# HC-base_revA.net
KiCad netlist of a schematic drawn in EAGLE
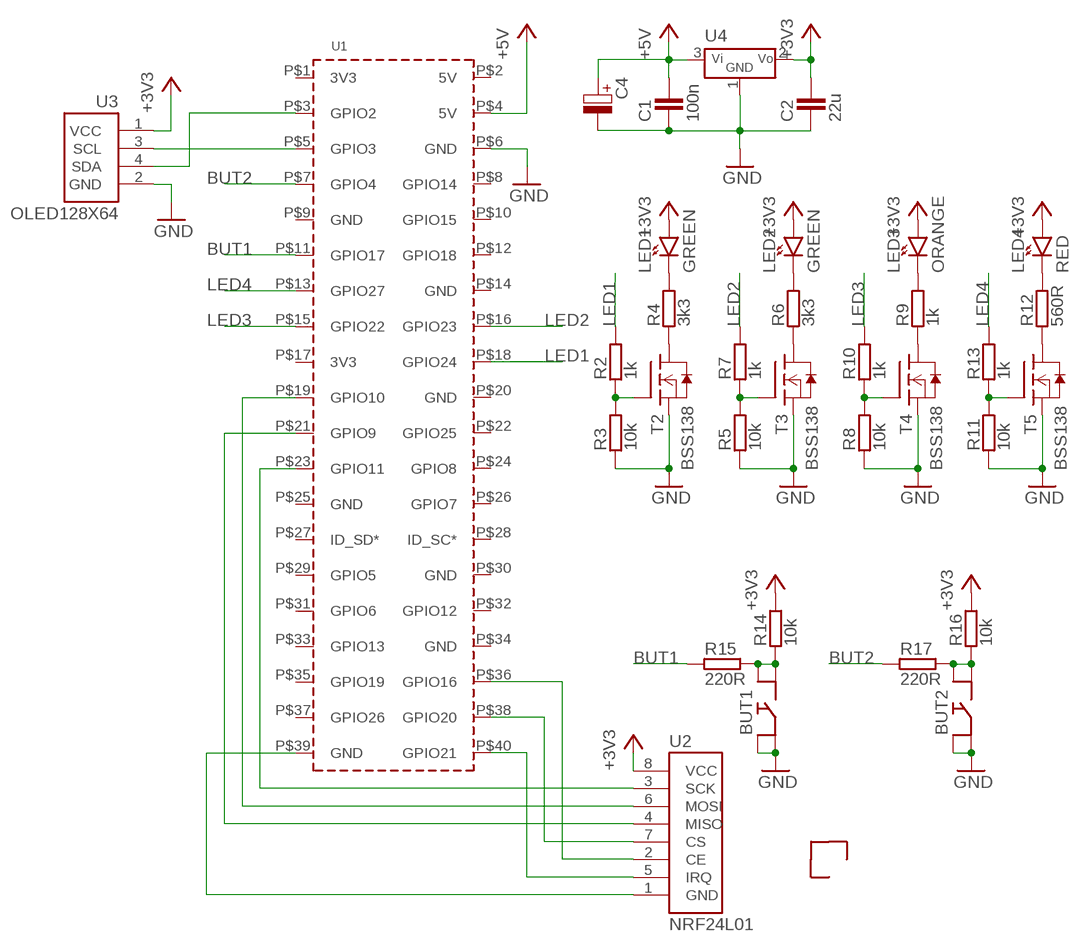
[diagram p0: schematic, sheet 1]

(export (version "E")
  (design (tool "Eeschema 10.0.6"))
  (components
    (comp (ref "BUT1")
      (value "BUTTON'SMD'")
      (footprint "eagle-import:BUTTON_SMD")
      (libsource (lib "eagle-import") (part "BUTTON'SMD'"))
    )
    (comp (ref "BUT2")
      (value "BUTTON'SMD'")
      (footprint "eagle-import:BUTTON_SMD")
      (libsource (lib "eagle-import") (part "BUTTON'SMD'"))
    )
    (comp (ref "C1")
      (value "100n")
      (footprint "eagle-import:C0805")
      (libsource (lib "eagle-import") (part "C-CERAMIC'SMD'"))
    )
    (comp (ref "C2")
      (value "22u")
      (footprint "eagle-import:C0805")
      (libsource (lib "eagle-import") (part "C-CERAMIC'SMD'"))
    )
    (comp (ref "C4")
      (value "C-POLY'6.5MM'")
      (footprint "eagle-import:ELYT-6MM5")
      (libsource (lib "eagle-import") (part "C-POLY'6.5MM'"))
    )
    (comp (ref "LED1")
      (value "GREEN")
      (footprint "eagle-import:LED0805")
      (libsource (lib "eagle-import") (part "LED'SMD'"))
    )
    (comp (ref "LED2")
      (value "GREEN")
      (footprint "eagle-import:LED0805")
      (libsource (lib "eagle-import") (part "LED'SMD'"))
    )
    (comp (ref "LED3")
      (value "ORANGE")
      (footprint "eagle-import:LED0805")
      (libsource (lib "eagle-import") (part "LED'SMD'"))
    )
    (comp (ref "LED4")
      (value "RED")
      (footprint "eagle-import:LED0805")
      (libsource (lib "eagle-import") (part "LED'SMD'"))
    )
    (comp (ref "R2")
      (value "1k")
      (footprint "eagle-import:R0805")
      (libsource (lib "eagle-import") (part "R'2'"))
    )
    (comp (ref "R3")
      (value "10k")
      (footprint "eagle-import:R0805")
      (libsource (lib "eagle-import") (part "R'2'"))
    )
    (comp (ref "R4")
      (value "3k3")
      (footprint "eagle-import:R0805")
      (libsource (lib "eagle-import") (part "R'2'"))
    )
    (comp (ref "R5")
      (value "10k")
      (footprint "eagle-import:R0805")
      (libsource (lib "eagle-import") (part "R'2'"))
    )
    (comp (ref "R6")
      (value "3k3")
      (footprint "eagle-import:R0805")
      (libsource (lib "eagle-import") (part "R'2'"))
    )
    (comp (ref "R7")
      (value "1k")
      (footprint "eagle-import:R0805")
      (libsource (lib "eagle-import") (part "R'2'"))
    )
    (comp (ref "R8")
      (value "10k")
      (footprint "eagle-import:R0805")
      (libsource (lib "eagle-import") (part "R'2'"))
    )
    (comp (ref "R9")
      (value "1k")
      (footprint "eagle-import:R0805")
      (libsource (lib "eagle-import") (part "R'2'"))
    )
    (comp (ref "R10")
      (value "1k")
      (footprint "eagle-import:R0805")
      (libsource (lib "eagle-import") (part "R'2'"))
    )
    (comp (ref "R11")
      (value "10k")
      (footprint "eagle-import:R0805")
      (libsource (lib "eagle-import") (part "R'2'"))
    )
    (comp (ref "R12")
      (value "560R")
      (footprint "eagle-import:R0805")
      (libsource (lib "eagle-import") (part "R'2'"))
    )
    (comp (ref "R13")
      (value "1k")
      (footprint "eagle-import:R0805")
      (libsource (lib "eagle-import") (part "R'2'"))
    )
    (comp (ref "R14")
      (value "10k")
      (footprint "eagle-import:R0805")
      (libsource (lib "eagle-import") (part "R'2'"))
    )
    (comp (ref "R15")
      (value "220R")
      (footprint "eagle-import:R0805")
      (libsource (lib "eagle-import") (part "R'2'"))
    )
    (comp (ref "R16")
      (value "10k")
      (footprint "eagle-import:R0805")
      (libsource (lib "eagle-import") (part "R'2'"))
    )
    (comp (ref "R17")
      (value "220R")
      (footprint "eagle-import:R0805")
      (libsource (lib "eagle-import") (part "R'2'"))
    )
    (comp (ref "T2")
      (value "BSS138")
      (footprint "eagle-import:SOT23")
      (libsource (lib "eagle-import") (part "BSS138"))
    )
    (comp (ref "T3")
      (value "BSS138")
      (footprint "eagle-import:SOT23")
      (libsource (lib "eagle-import") (part "BSS138"))
    )
    (comp (ref "T4")
      (value "BSS138")
      (footprint "eagle-import:SOT23")
      (libsource (lib "eagle-import") (part "BSS138"))
    )
    (comp (ref "T5")
      (value "BSS138")
      (footprint "eagle-import:SOT23")
      (libsource (lib "eagle-import") (part "BSS138"))
    )
    (comp (ref "U$1")
      (value "CORNER")
      (footprint "eagle-import:CORNER")
      (libsource (lib "eagle-import") (part "CORNER"))
    )
    (comp (ref "U$2")
      (value "CORNER")
      (footprint "eagle-import:CORNER")
      (libsource (lib "eagle-import") (part "CORNER"))
    )
    (comp (ref "U$3")
      (value "CORNER")
      (footprint "eagle-import:CORNER")
      (libsource (lib "eagle-import") (part "CORNER"))
    )
    (comp (ref "U1")
      (value "RPI3_SIMPLE'PART'")
      (footprint "eagle-import:RPI3-PART")
      (libsource (lib "eagle-import") (part "RPI3_SIMPLE'PART'"))
    )
    (comp (ref "U2")
      (value "NRF24L01")
      (footprint "eagle-import:NRF24L01")
      (libsource (lib "eagle-import") (part "NRF24L01"))
    )
    (comp (ref "U3")
      (value "OLED128X64")
      (footprint "eagle-import:OLED128X64")
      (libsource (lib "eagle-import") (part "OLED128X64"))
    )
    (comp (ref "U4")
      (value "V_STAB'TS1117'")
      (footprint "eagle-import:SOT223")
      (libsource (lib "eagle-import") (part "V_STAB'TS1117'"))
    )
  )
  (nets
    (net (code "1") (name "+3V3") (class "Default")
      (node (ref "C2") (pin "2") (pinfunction "P$2_2") (pintype "bidirectional"))
      (node (ref "LED1") (pin "1") (pinfunction "A_1") (pintype "bidirectional"))
      (node (ref "LED2") (pin "1") (pinfunction "A_1") (pintype "bidirectional"))
      (node (ref "LED3") (pin "1") (pinfunction "A_1") (pintype "bidirectional"))
      (node (ref "LED4") (pin "1") (pinfunction "A_1") (pintype "bidirectional"))
      (node (ref "R14") (pin "2") (pinfunction "P$2_2") (pintype "bidirectional"))
      (node (ref "R16") (pin "2") (pinfunction "P$2_2") (pintype "bidirectional"))
      (node (ref "U2") (pin "8") (pinfunction "VCC_8") (pintype "power_in"))
      (node (ref "U3") (pin "1") (pinfunction "VCC_1") (pintype "power_in"))
      (node (ref "U4") (pin "2") (pinfunction "VOUT_2") (pintype "power_in"))
    )
    (net (code "2") (name "+5V") (class "Default")
      (node (ref "C1") (pin "2") (pinfunction "P$2_2") (pintype "bidirectional"))
      (node (ref "C4") (pin "+") (pinfunction "POS_+") (pintype "bidirectional"))
      (node (ref "U1") (pin "P$4") (pinfunction "5V_P$4") (pintype "bidirectional"))
      (node (ref "U4") (pin "3") (pinfunction "VIN_3") (pintype "power_in"))
    )
    (net (code "3") (name "/BUT1") (class "Default")
      (node (ref "R15") (pin "1") (pinfunction "P$1_1") (pintype "bidirectional"))
      (node (ref "U1") (pin "P$11") (pinfunction "GPIO17_P$11") (pintype "bidirectional"))
    )
    (net (code "4") (name "/BUT2") (class "Default")
      (node (ref "R17") (pin "1") (pinfunction "P$1_1") (pintype "bidirectional"))
      (node (ref "U1") (pin "P$7") (pinfunction "GPIO4_P$7") (pintype "bidirectional"))
    )
    (net (code "5") (name "/LED1") (class "Default")
      (node (ref "R2") (pin "2") (pinfunction "P$2_2") (pintype "bidirectional"))
      (node (ref "U1") (pin "P$18") (pinfunction "GPIO24_P$18") (pintype "bidirectional"))
    )
    (net (code "6") (name "/LED2") (class "Default")
      (node (ref "R7") (pin "2") (pinfunction "P$2_2") (pintype "bidirectional"))
      (node (ref "U1") (pin "P$16") (pinfunction "GPIO23_P$16") (pintype "bidirectional"))
    )
    (net (code "7") (name "/LED3") (class "Default")
      (node (ref "R10") (pin "2") (pinfunction "P$2_2") (pintype "bidirectional"))
      (node (ref "U1") (pin "P$15") (pinfunction "GPIO22_P$15") (pintype "bidirectional"))
    )
    (net (code "8") (name "/LED4") (class "Default")
      (node (ref "R13") (pin "2") (pinfunction "P$2_2") (pintype "bidirectional"))
      (node (ref "U1") (pin "P$13") (pinfunction "GPIO27_P$13") (pintype "bidirectional"))
    )
    (net (code "9") (name "GND") (class "Default")
      (node (ref "BUT1") (pin "1") (pinfunction "4_1") (pintype "bidirectional"))
      (node (ref "BUT1") (pin "2") (pinfunction "2_2") (pintype "bidirectional"))
      (node (ref "BUT2") (pin "1") (pinfunction "4_1") (pintype "bidirectional"))
      (node (ref "BUT2") (pin "2") (pinfunction "2_2") (pintype "bidirectional"))
      (node (ref "C1") (pin "1") (pinfunction "P$1_1") (pintype "bidirectional"))
      (node (ref "C2") (pin "1") (pinfunction "P$1_1") (pintype "bidirectional"))
      (node (ref "C4") (pin "-") (pinfunction "NEG_-") (pintype "bidirectional"))
      (node (ref "R11") (pin "1") (pinfunction "P$1_1") (pintype "bidirectional"))
      (node (ref "R3") (pin "1") (pinfunction "P$1_1") (pintype "bidirectional"))
      (node (ref "R5") (pin "1") (pinfunction "P$1_1") (pintype "bidirectional"))
      (node (ref "R8") (pin "1") (pinfunction "P$1_1") (pintype "bidirectional"))
      (node (ref "T2") (pin "2") (pinfunction "S_2") (pintype "passive"))
      (node (ref "T3") (pin "2") (pinfunction "S_2") (pintype "passive"))
      (node (ref "T4") (pin "2") (pinfunction "S_2") (pintype "passive"))
      (node (ref "T5") (pin "2") (pinfunction "S_2") (pintype "passive"))
      (node (ref "U1") (pin "P$6") (pinfunction "GND_P$6") (pintype "bidirectional"))
      (node (ref "U3") (pin "2") (pinfunction "GND_2") (pintype "power_in"))
      (node (ref "U4") (pin "1") (pinfunction "GND_1") (pintype "power_in"))
    )
    (net (code "10") (name "Net-(BUT1-1)") (class "Default")
      (node (ref "BUT1") (pin "3") (pinfunction "1_3") (pintype "bidirectional"))
      (node (ref "BUT1") (pin "4") (pinfunction "3_4") (pintype "bidirectional"))
      (node (ref "R14") (pin "1") (pinfunction "P$1_1") (pintype "bidirectional"))
      (node (ref "R15") (pin "2") (pinfunction "P$2_2") (pintype "bidirectional"))
    )
    (net (code "11") (name "Net-(BUT2-1)") (class "Default")
      (node (ref "BUT2") (pin "3") (pinfunction "1_3") (pintype "bidirectional"))
      (node (ref "BUT2") (pin "4") (pinfunction "3_4") (pintype "bidirectional"))
      (node (ref "R16") (pin "1") (pinfunction "P$1_1") (pintype "bidirectional"))
      (node (ref "R17") (pin "2") (pinfunction "P$2_2") (pintype "bidirectional"))
    )
    (net (code "12") (name "Net-(LED1-K)") (class "Default")
      (node (ref "LED1") (pin "2") (pinfunction "K_2") (pintype "bidirectional"))
      (node (ref "R4") (pin "2") (pinfunction "P$2_2") (pintype "bidirectional"))
    )
    (net (code "13") (name "Net-(LED2-K)") (class "Default")
      (node (ref "LED2") (pin "2") (pinfunction "K_2") (pintype "bidirectional"))
      (node (ref "R6") (pin "2") (pinfunction "P$2_2") (pintype "bidirectional"))
    )
    (net (code "14") (name "Net-(LED3-K)") (class "Default")
      (node (ref "LED3") (pin "2") (pinfunction "K_2") (pintype "bidirectional"))
      (node (ref "R9") (pin "2") (pinfunction "P$2_2") (pintype "bidirectional"))
    )
    (net (code "15") (name "Net-(LED4-K)") (class "Default")
      (node (ref "LED4") (pin "2") (pinfunction "K_2") (pintype "bidirectional"))
      (node (ref "R12") (pin "2") (pinfunction "P$2_2") (pintype "bidirectional"))
    )
    (net (code "16") (name "Net-(R2-P$1)") (class "Default")
      (node (ref "R2") (pin "1") (pinfunction "P$1_1") (pintype "bidirectional"))
      (node (ref "R3") (pin "2") (pinfunction "P$2_2") (pintype "bidirectional"))
      (node (ref "T2") (pin "1") (pinfunction "G_1") (pintype "passive"))
    )
    (net (code "17") (name "Net-(R4-P$1)") (class "Default")
      (node (ref "R4") (pin "1") (pinfunction "P$1_1") (pintype "bidirectional"))
      (node (ref "T2") (pin "3") (pinfunction "D_3") (pintype "passive"))
    )
    (net (code "18") (name "Net-(R5-P$2)") (class "Default")
      (node (ref "R5") (pin "2") (pinfunction "P$2_2") (pintype "bidirectional"))
      (node (ref "R7") (pin "1") (pinfunction "P$1_1") (pintype "bidirectional"))
      (node (ref "T3") (pin "1") (pinfunction "G_1") (pintype "passive"))
    )
    (net (code "19") (name "Net-(R6-P$1)") (class "Default")
      (node (ref "R6") (pin "1") (pinfunction "P$1_1") (pintype "bidirectional"))
      (node (ref "T3") (pin "3") (pinfunction "D_3") (pintype "passive"))
    )
    (net (code "20") (name "Net-(R9-P$1)") (class "Default")
      (node (ref "R9") (pin "1") (pinfunction "P$1_1") (pintype "bidirectional"))
      (node (ref "T4") (pin "3") (pinfunction "D_3") (pintype "passive"))
    )
    (net (code "21") (name "Net-(R10-P$1)") (class "Default")
      (node (ref "R10") (pin "1") (pinfunction "P$1_1") (pintype "bidirectional"))
      (node (ref "R8") (pin "2") (pinfunction "P$2_2") (pintype "bidirectional"))
      (node (ref "T4") (pin "1") (pinfunction "G_1") (pintype "passive"))
    )
    (net (code "22") (name "Net-(R11-P$2)") (class "Default")
      (node (ref "R11") (pin "2") (pinfunction "P$2_2") (pintype "bidirectional"))
      (node (ref "R13") (pin "1") (pinfunction "P$1_1") (pintype "bidirectional"))
      (node (ref "T5") (pin "1") (pinfunction "G_1") (pintype "passive"))
    )
    (net (code "23") (name "Net-(R12-P$1)") (class "Default")
      (node (ref "R12") (pin "1") (pinfunction "P$1_1") (pintype "bidirectional"))
      (node (ref "T5") (pin "3") (pinfunction "D_3") (pintype "passive"))
    )
    (net (code "24") (name "Net-(U1-GPIO2)") (class "Default")
      (node (ref "U1") (pin "P$3") (pinfunction "GPIO2_P$3") (pintype "bidirectional"))
      (node (ref "U3") (pin "4") (pinfunction "SDA_4") (pintype "bidirectional"))
    )
    (net (code "25") (name "Net-(U1-GPIO3)") (class "Default")
      (node (ref "U1") (pin "P$5") (pinfunction "GPIO3_P$5") (pintype "bidirectional"))
      (node (ref "U3") (pin "3") (pinfunction "SCL_3") (pintype "bidirectional"))
    )
    (net (code "26") (name "Net-(U1-GPIO9)") (class "Default")
      (node (ref "U1") (pin "P$21") (pinfunction "GPIO9_P$21") (pintype "bidirectional"))
      (node (ref "U2") (pin "4") (pinfunction "MISO_4") (pintype "bidirectional"))
    )
    (net (code "27") (name "Net-(U1-GPIO10)") (class "Default")
      (node (ref "U1") (pin "P$19") (pinfunction "GPIO10_P$19") (pintype "bidirectional"))
      (node (ref "U2") (pin "6") (pinfunction "MOSI_6") (pintype "bidirectional"))
    )
    (net (code "28") (name "Net-(U1-GPIO11)") (class "Default")
      (node (ref "U1") (pin "P$23") (pinfunction "GPIO11_P$23") (pintype "bidirectional"))
      (node (ref "U2") (pin "3") (pinfunction "SCK_3") (pintype "bidirectional"))
    )
    (net (code "29") (name "Net-(U1-GPIO16)") (class "Default")
      (node (ref "U1") (pin "P$36") (pinfunction "GPIO16_P$36") (pintype "bidirectional"))
      (node (ref "U2") (pin "2") (pinfunction "CE_2") (pintype "bidirectional"))
    )
    (net (code "30") (name "Net-(U1-GPIO20)") (class "Default")
      (node (ref "U1") (pin "P$38") (pinfunction "GPIO20_P$38") (pintype "bidirectional"))
      (node (ref "U2") (pin "7") (pinfunction "CS_7") (pintype "bidirectional"))
    )
    (net (code "31") (name "Net-(U1-GPIO21)") (class "Default")
      (node (ref "U1") (pin "P$40") (pinfunction "GPIO21_P$40") (pintype "bidirectional"))
      (node (ref "U2") (pin "5") (pinfunction "IRQ_5") (pintype "bidirectional"))
    )
    (net (code "32") (name "Net-(U2-GND)") (class "Default")
      (node (ref "U1") (pin "P$39") (pinfunction "GND_P$39") (pintype "bidirectional"))
      (node (ref "U2") (pin "1") (pinfunction "GND_1") (pintype "power_in"))
    )
    (net (code "33") (name "unconnected-(U1-3V3-PadP$1)") (class "Default")
      (node (ref "U1") (pin "P$1") (pinfunction "3V3_P$1") (pintype "bidirectional"))
    )
    (net (code "34") (name "unconnected-(U1-3V3-PadP$17)") (class "Default")
      (node (ref "U1") (pin "P$17") (pinfunction "3V3_P$17") (pintype "bidirectional"))
    )
    (net (code "35") (name "unconnected-(U1-5V-PadP$2)") (class "Default")
      (node (ref "U1") (pin "P$2") (pinfunction "5V_P$2") (pintype "bidirectional"))
    )
    (net (code "36") (name "unconnected-(U1-GND-PadP$9)") (class "Default")
      (node (ref "U1") (pin "P$9") (pinfunction "GND_P$9") (pintype "bidirectional"))
    )
    (net (code "37") (name "unconnected-(U1-GND-PadP$14)") (class "Default")
      (node (ref "U1") (pin "P$14") (pinfunction "GND_P$14") (pintype "bidirectional"))
    )
    (net (code "38") (name "unconnected-(U1-GND-PadP$20)") (class "Default")
      (node (ref "U1") (pin "P$20") (pinfunction "GND_P$20") (pintype "bidirectional"))
    )
    (net (code "39") (name "unconnected-(U1-GND-PadP$25)") (class "Default")
      (node (ref "U1") (pin "P$25") (pinfunction "GND_P$25") (pintype "bidirectional"))
    )
    (net (code "40") (name "unconnected-(U1-GND-PadP$30)") (class "Default")
      (node (ref "U1") (pin "P$30") (pinfunction "GND_P$30") (pintype "bidirectional"))
    )
    (net (code "41") (name "unconnected-(U1-GND-PadP$34)") (class "Default")
      (node (ref "U1") (pin "P$34") (pinfunction "GND_P$34") (pintype "bidirectional"))
    )
    (net (code "42") (name "unconnected-(U1-GPIO5-PadP$29)") (class "Default")
      (node (ref "U1") (pin "P$29") (pinfunction "GPIO5_P$29") (pintype "bidirectional"))
    )
    (net (code "43") (name "unconnected-(U1-GPIO6-PadP$31)") (class "Default")
      (node (ref "U1") (pin "P$31") (pinfunction "GPIO6_P$31") (pintype "bidirectional"))
    )
    (net (code "44") (name "unconnected-(U1-GPIO7-PadP$26)") (class "Default")
      (node (ref "U1") (pin "P$26") (pinfunction "GPIO7_P$26") (pintype "bidirectional"))
    )
    (net (code "45") (name "unconnected-(U1-GPIO8-PadP$24)") (class "Default")
      (node (ref "U1") (pin "P$24") (pinfunction "GPIO8_P$24") (pintype "bidirectional"))
    )
    (net (code "46") (name "unconnected-(U1-GPIO12-PadP$32)") (class "Default")
      (node (ref "U1") (pin "P$32") (pinfunction "GPIO12_P$32") (pintype "bidirectional"))
    )
    (net (code "47") (name "unconnected-(U1-GPIO13-PadP$33)") (class "Default")
      (node (ref "U1") (pin "P$33") (pinfunction "GPIO13_P$33") (pintype "bidirectional"))
    )
    (net (code "48") (name "unconnected-(U1-GPIO14-PadP$8)") (class "Default")
      (node (ref "U1") (pin "P$8") (pinfunction "GPIO14_P$8") (pintype "bidirectional"))
    )
    (net (code "49") (name "unconnected-(U1-GPIO15-PadP$10)") (class "Default")
      (node (ref "U1") (pin "P$10") (pinfunction "GPIO15_P$10") (pintype "bidirectional"))
    )
    (net (code "50") (name "unconnected-(U1-GPIO18-PadP$12)") (class "Default")
      (node (ref "U1") (pin "P$12") (pinfunction "GPIO18_P$12") (pintype "bidirectional"))
    )
    (net (code "51") (name "unconnected-(U1-GPIO19-PadP$35)") (class "Default")
      (node (ref "U1") (pin "P$35") (pinfunction "GPIO19_P$35") (pintype "bidirectional"))
    )
    (net (code "52") (name "unconnected-(U1-GPIO25-PadP$22)") (class "Default")
      (node (ref "U1") (pin "P$22") (pinfunction "GPIO25_P$22") (pintype "bidirectional"))
    )
    (net (code "53") (name "unconnected-(U1-GPIO26-PadP$37)") (class "Default")
      (node (ref "U1") (pin "P$37") (pinfunction "GPIO26_P$37") (pintype "bidirectional"))
    )
    (net (code "54") (name "unconnected-(U1-ID_SC*-PadP$28)") (class "Default")
      (node (ref "U1") (pin "P$28") (pinfunction "ID_SC*_P$28") (pintype "bidirectional"))
    )
    (net (code "55") (name "unconnected-(U1-ID_SD*-PadP$27)") (class "Default")
      (node (ref "U1") (pin "P$27") (pinfunction "ID_SD*_P$27") (pintype "bidirectional"))
    )
  )
)
